# 02-Clocks.net
KiCad netlist of a schematic drawn in Altium Designer
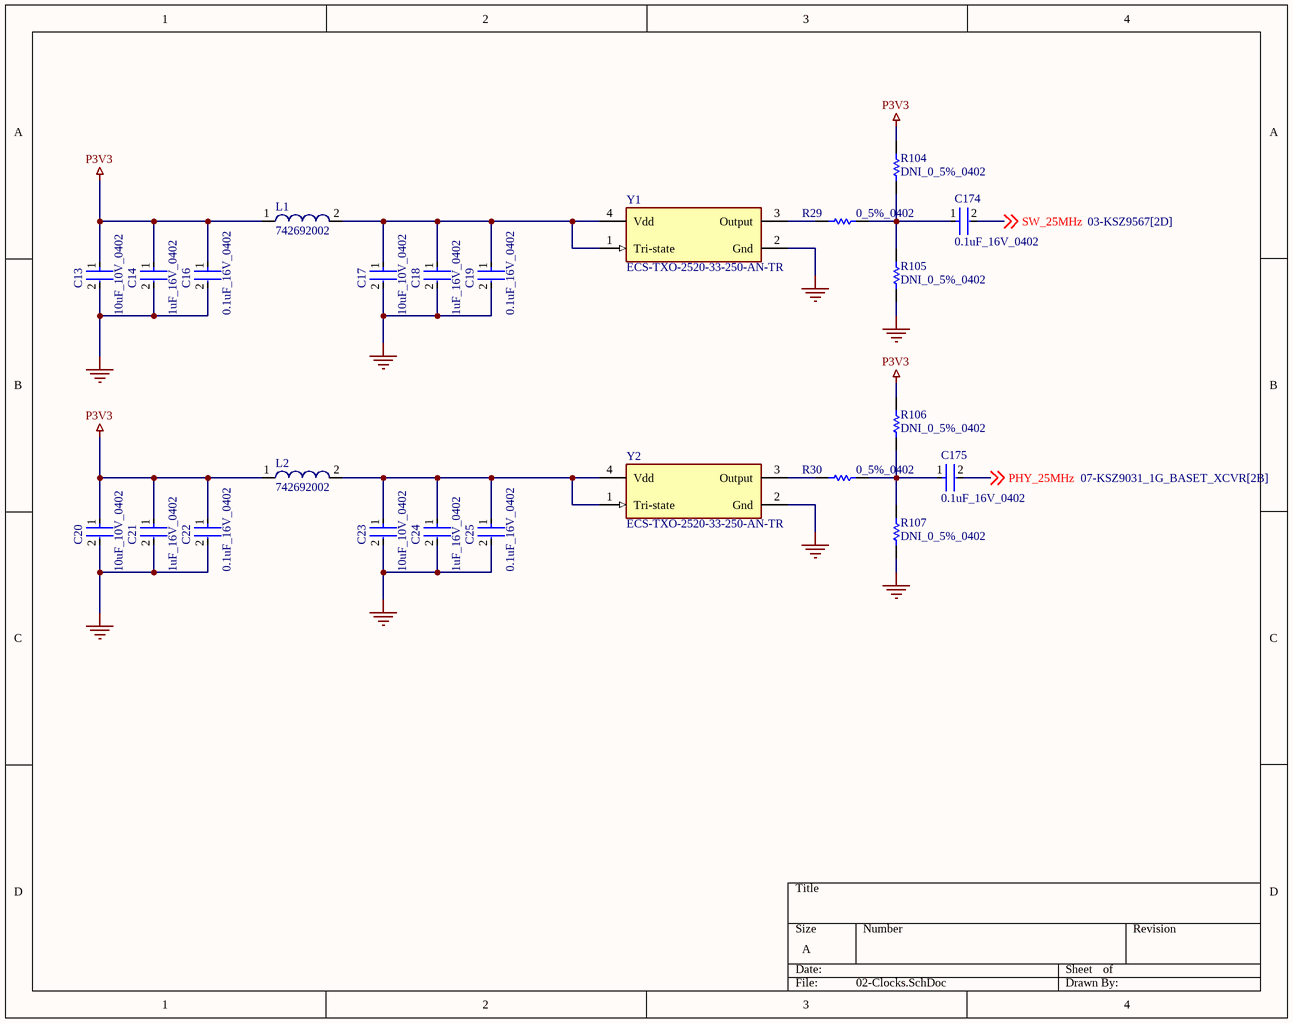
[diagram p0: 02-Clocks.SchDoc]

(export (version "E")
  (design (tool "Eeschema 10.0.6"))
  (components
    (comp (ref "C13")
      (value "10uF_10V_0402")
      (footprint "FP-CL05A106MP5NUNC-MFG")
      (description "CAP CER 10UF 10V X5R 0402")
      (fields
        (field (name "OCTOPART") "https://octopart.com/cl05a106mp5nunc-samsung-22457395")
        (field (name "TOLERANCE") "20%")
      )
      (libsource (lib "Altium Content Vault") (part "b4654b650e69147ec39a6b967a45e02"))
    )
    (comp (ref "C14")
      (value "1uF_16V_0402")
      (footprint "FP-0402-L_1_0_0_05-W_0_5-IPC_A")
      (description "None")
      (fields (field (name "TOLERANCE") "10%"))
      (libsource (lib "Altium Content Vault") (part "b4654b650e69147ec39a6b967a45e02"))
    )
    (comp (ref "C16")
      (value "0.1uF_16V_0402")
      (footprint "FP-C0402-BB-MFG")
      (description "CAP CER 0.1UF 16V 5% X7R 0402")
      (fields
        (field (name "MANUFACTURER") "Kemet")
        (field (name "MANUFACTURER PART NUMBER") "C0402C104J4RACTU")
      )
      (libsource (lib "Altium Content Vault") (part "b4654b650e69147ec39a6b967a45e02"))
    )
    (comp (ref "C17")
      (value "10uF_10V_0402")
      (footprint "FP-CL05A106MP5NUNC-MFG")
      (description "CAP CER 10UF 10V X5R 0402")
      (fields
        (field (name "OCTOPART") "https://octopart.com/cl05a106mp5nunc-samsung-22457395")
        (field (name "TOLERANCE") "20%")
      )
      (libsource (lib "Altium Content Vault") (part "b4654b650e69147ec39a6b967a45e02"))
    )
    (comp (ref "C18")
      (value "1uF_16V_0402")
      (footprint "FP-0402-L_1_0_0_05-W_0_5-IPC_A")
      (description "None")
      (fields (field (name "TOLERANCE") "10%"))
      (libsource (lib "Altium Content Vault") (part "b4654b650e69147ec39a6b967a45e02"))
    )
    (comp (ref "C19")
      (value "0.1uF_16V_0402")
      (footprint "FP-C0402-BB-MFG")
      (description "CAP CER 0.1UF 16V 5% X7R 0402")
      (fields
        (field (name "MANUFACTURER") "Kemet")
        (field (name "MANUFACTURER PART NUMBER") "C0402C104J4RACTU")
      )
      (libsource (lib "Altium Content Vault") (part "b4654b650e69147ec39a6b967a45e02"))
    )
    (comp (ref "C20")
      (value "10uF_10V_0402")
      (footprint "FP-CL05A106MP5NUNC-MFG")
      (description "CAP CER 10UF 10V X5R 0402")
      (fields
        (field (name "OCTOPART") "https://octopart.com/cl05a106mp5nunc-samsung-22457395")
        (field (name "TOLERANCE") "20%")
      )
      (libsource (lib "Altium Content Vault") (part "b4654b650e69147ec39a6b967a45e02"))
    )
    (comp (ref "C21")
      (value "1uF_16V_0402")
      (footprint "FP-0402-L_1_0_0_05-W_0_5-IPC_A")
      (description "None")
      (fields (field (name "TOLERANCE") "10%"))
      (libsource (lib "Altium Content Vault") (part "b4654b650e69147ec39a6b967a45e02"))
    )
    (comp (ref "C22")
      (value "0.1uF_16V_0402")
      (footprint "FP-C0402-BB-MFG")
      (description "CAP CER 0.1UF 16V 5% X7R 0402")
      (fields
        (field (name "MANUFACTURER") "Kemet")
        (field (name "MANUFACTURER PART NUMBER") "C0402C104J4RACTU")
      )
      (libsource (lib "Altium Content Vault") (part "b4654b650e69147ec39a6b967a45e02"))
    )
    (comp (ref "C23")
      (value "10uF_10V_0402")
      (footprint "FP-CL05A106MP5NUNC-MFG")
      (description "CAP CER 10UF 10V X5R 0402")
      (fields
        (field (name "OCTOPART") "https://octopart.com/cl05a106mp5nunc-samsung-22457395")
        (field (name "TOLERANCE") "20%")
      )
      (libsource (lib "Altium Content Vault") (part "b4654b650e69147ec39a6b967a45e02"))
    )
    (comp (ref "C24")
      (value "1uF_16V_0402")
      (footprint "FP-0402-L_1_0_0_05-W_0_5-IPC_A")
      (description "None")
      (fields (field (name "TOLERANCE") "10%"))
      (libsource (lib "Altium Content Vault") (part "b4654b650e69147ec39a6b967a45e02"))
    )
    (comp (ref "C25")
      (value "0.1uF_16V_0402")
      (footprint "FP-C0402-BB-MFG")
      (description "CAP CER 0.1UF 16V 5% X7R 0402")
      (fields
        (field (name "MANUFACTURER") "Kemet")
        (field (name "MANUFACTURER PART NUMBER") "C0402C104J4RACTU")
      )
      (libsource (lib "Altium Content Vault") (part "b4654b650e69147ec39a6b967a45e02"))
    )
    (comp (ref "C174")
      (value "0.1uF_16V_0402")
      (footprint "FP-C0402-BB-MFG")
      (description "CAP CER 0.1UF 16V 5% X7R 0402")
      (fields
        (field (name "MANUFACTURER") "Kemet")
        (field (name "MANUFACTURER PART NUMBER") "C0402C104J4RACTU")
      )
      (libsource (lib "Altium Content Vault") (part "b4654b650e69147ec39a6b967a45e02"))
    )
    (comp (ref "C175")
      (value "0.1uF_16V_0402")
      (footprint "FP-C0402-BB-MFG")
      (description "CAP CER 0.1UF 16V 5% X7R 0402")
      (fields
        (field (name "MANUFACTURER") "Kemet")
        (field (name "MANUFACTURER PART NUMBER") "C0402C104J4RACTU")
      )
      (libsource (lib "Altium Content Vault") (part "b4654b650e69147ec39a6b967a45e02"))
    )
    (comp (ref "L1")
      (value "742692002")
      (footprint "WE-TMSB 0201")
      (description "Tiny Multilayer Suppression  Bead  WE-TMSB, Z= 60 Ohm")
      (fields (field (name "MANUFACTURER") "Wuerth Elektronik"))
      (libsource (lib "Altium Content Vault") (part "WE-IND-INDUCTOR-2"))
    )
    (comp (ref "L2")
      (value "742692002")
      (footprint "WE-TMSB 0201")
      (description "Tiny Multilayer Suppression  Bead  WE-TMSB, Z= 60 Ohm")
      (fields (field (name "MANUFACTURER") "Wuerth Elektronik"))
      (libsource (lib "Altium Content Vault") (part "WE-IND-INDUCTOR-2"))
    )
    (comp (ref "R29")
      (value "0_5%_0402")
      (footprint "RESC1005X40X25NL05T10")
      (fields (field (name "MANUFACTURER") "Panasonic") (field (name "PART NUMBER") "ERJ-U020R00X"))
      (libsource (lib "Altium Content Vault") (part "RES"))
    )
    (comp (ref "R30")
      (value "0_5%_0402")
      (footprint "RESC1005X40X25NL05T10")
      (fields (field (name "MANUFACTURER") "Panasonic") (field (name "PART NUMBER") "ERJ-U020R00X"))
      (libsource (lib "Altium Content Vault") (part "RES"))
    )
    (comp (ref "R104")
      (value "DNI_0_5%_0402")
      (footprint "RESC1005X40X25NL05T10")
      (fields (field (name "MANUFACTURER") "Panasonic") (field (name "PART NUMBER") "ERJ-U020R00X"))
      (libsource (lib "Altium Content Vault") (part "RES"))
    )
    (comp (ref "R105")
      (value "DNI_0_5%_0402")
      (footprint "RESC1005X40X25NL05T10")
      (fields (field (name "MANUFACTURER") "Panasonic") (field (name "PART NUMBER") "ERJ-U020R00X"))
      (libsource (lib "Altium Content Vault") (part "RES"))
    )
    (comp (ref "R106")
      (value "DNI_0_5%_0402")
      (footprint "RESC1005X40X25NL05T10")
      (fields (field (name "MANUFACTURER") "Panasonic") (field (name "PART NUMBER") "ERJ-U020R00X"))
      (libsource (lib "Altium Content Vault") (part "RES"))
    )
    (comp (ref "R107")
      (value "DNI_0_5%_0402")
      (footprint "RESC1005X40X25NL05T10")
      (fields (field (name "MANUFACTURER") "Panasonic") (field (name "PART NUMBER") "ERJ-U020R00X"))
      (libsource (lib "Altium Content Vault") (part "RES"))
    )
    (comp (ref "Y1")
      (value "ECS-TXO-2520-33-250-AN-TR")
      (footprint "FP-ECS-TXO-2520-MFG")
      (description "XTAL OSC TCXO 25.0000MHZ HCMOS")
      (libsource (lib "Altium Content Vault") (part "04cd953f3cf158082f8c09fbdb924ef"))
    )
    (comp (ref "Y2")
      (value "ECS-TXO-2520-33-250-AN-TR")
      (footprint "FP-ECS-TXO-2520-MFG")
      (description "XTAL OSC TCXO 25.0000MHZ HCMOS")
      (libsource (lib "Altium Content Vault") (part "04cd953f3cf158082f8c09fbdb924ef"))
    )
  )
  (nets
    (net (code "1") (name "GND") (class "Default")
      (node (ref "C13") (pin "2") (pinfunction "2_2") (pintype "passive"))
      (node (ref "C14") (pin "2") (pinfunction "2_2") (pintype "passive"))
      (node (ref "C16") (pin "2") (pinfunction "2_2") (pintype "passive"))
      (node (ref "C17") (pin "2") (pinfunction "2_2") (pintype "passive"))
      (node (ref "C18") (pin "2") (pinfunction "2_2") (pintype "passive"))
      (node (ref "C19") (pin "2") (pinfunction "2_2") (pintype "passive"))
      (node (ref "C20") (pin "2") (pinfunction "2_2") (pintype "passive"))
      (node (ref "C21") (pin "2") (pinfunction "2_2") (pintype "passive"))
      (node (ref "C22") (pin "2") (pinfunction "2_2") (pintype "passive"))
      (node (ref "C23") (pin "2") (pinfunction "2_2") (pintype "passive"))
      (node (ref "C24") (pin "2") (pinfunction "2_2") (pintype "passive"))
      (node (ref "C25") (pin "2") (pinfunction "2_2") (pintype "passive"))
      (node (ref "R105") (pin "1") (pinfunction "1_1") (pintype "passive"))
      (node (ref "R107") (pin "1") (pinfunction "1_1") (pintype "passive"))
      (node (ref "Y1") (pin "2") (pinfunction "Gnd_2") (pintype "power_in"))
      (node (ref "Y2") (pin "2") (pinfunction "Gnd_2") (pintype "power_in"))
    )
    (net (code "2") (name "Net-(C174-Pad1)") (class "Default")
      (node (ref "C174") (pin "1") (pinfunction "1_1") (pintype "passive"))
      (node (ref "R104") (pin "1") (pinfunction "1_1") (pintype "passive"))
      (node (ref "R105") (pin "2") (pinfunction "2_2") (pintype "passive"))
      (node (ref "R29") (pin "2") (pinfunction "2_2") (pintype "passive"))
    )
    (net (code "3") (name "Net-(C175-Pad1)") (class "Default")
      (node (ref "C175") (pin "1") (pinfunction "1_1") (pintype "passive"))
      (node (ref "R106") (pin "1") (pinfunction "1_1") (pintype "passive"))
      (node (ref "R107") (pin "2") (pinfunction "2_2") (pintype "passive"))
      (node (ref "R30") (pin "2") (pinfunction "2_2") (pintype "passive"))
    )
    (net (code "4") (name "Net-(Y1-Output)") (class "Default")
      (node (ref "R29") (pin "1") (pinfunction "1_1") (pintype "passive"))
      (node (ref "Y1") (pin "3") (pinfunction "Output_3") (pintype "tri_state"))
    )
    (net (code "5") (name "Net-(Y1-Tri-state)") (class "Default")
      (node (ref "C17") (pin "1") (pinfunction "1_1") (pintype "passive"))
      (node (ref "C18") (pin "1") (pinfunction "1_1") (pintype "passive"))
      (node (ref "C19") (pin "1") (pinfunction "1_1") (pintype "passive"))
      (node (ref "L1") (pin "2") (pinfunction "2_2") (pintype "passive"))
      (node (ref "Y1") (pin "1") (pinfunction "Tri-state_1") (pintype "input"))
      (node (ref "Y1") (pin "4") (pinfunction "Vdd_4") (pintype "power_in"))
    )
    (net (code "6") (name "Net-(Y2-Output)") (class "Default")
      (node (ref "R30") (pin "1") (pinfunction "1_1") (pintype "passive"))
      (node (ref "Y2") (pin "3") (pinfunction "Output_3") (pintype "tri_state"))
    )
    (net (code "7") (name "Net-(Y2-Tri-state)") (class "Default")
      (node (ref "C23") (pin "1") (pinfunction "1_1") (pintype "passive"))
      (node (ref "C24") (pin "1") (pinfunction "1_1") (pintype "passive"))
      (node (ref "C25") (pin "1") (pinfunction "1_1") (pintype "passive"))
      (node (ref "L2") (pin "2") (pinfunction "2_2") (pintype "passive"))
      (node (ref "Y2") (pin "1") (pinfunction "Tri-state_1") (pintype "input"))
      (node (ref "Y2") (pin "4") (pinfunction "Vdd_4") (pintype "power_in"))
    )
    (net (code "8") (name "P3V3") (class "Default")
      (node (ref "C13") (pin "1") (pinfunction "1_1") (pintype "passive"))
      (node (ref "C14") (pin "1") (pinfunction "1_1") (pintype "passive"))
      (node (ref "C16") (pin "1") (pinfunction "1_1") (pintype "passive"))
      (node (ref "C20") (pin "1") (pinfunction "1_1") (pintype "passive"))
      (node (ref "C21") (pin "1") (pinfunction "1_1") (pintype "passive"))
      (node (ref "C22") (pin "1") (pinfunction "1_1") (pintype "passive"))
      (node (ref "L1") (pin "1") (pinfunction "1_1") (pintype "passive"))
      (node (ref "L2") (pin "1") (pinfunction "1_1") (pintype "passive"))
      (node (ref "R104") (pin "2") (pinfunction "2_2") (pintype "passive"))
      (node (ref "R106") (pin "2") (pinfunction "2_2") (pintype "passive"))
    )
    (net (code "9") (name "PHY_25MHz") (class "Default")
      (node (ref "C175") (pin "2") (pinfunction "2_2") (pintype "passive"))
    )
    (net (code "10") (name "SW_25MHz") (class "Default")
      (node (ref "C174") (pin "2") (pinfunction "2_2") (pintype "passive"))
    )
  )
)
